# 6coils-1-discrete.net
KiCad netlist of a schematic drawn in EasyEDA
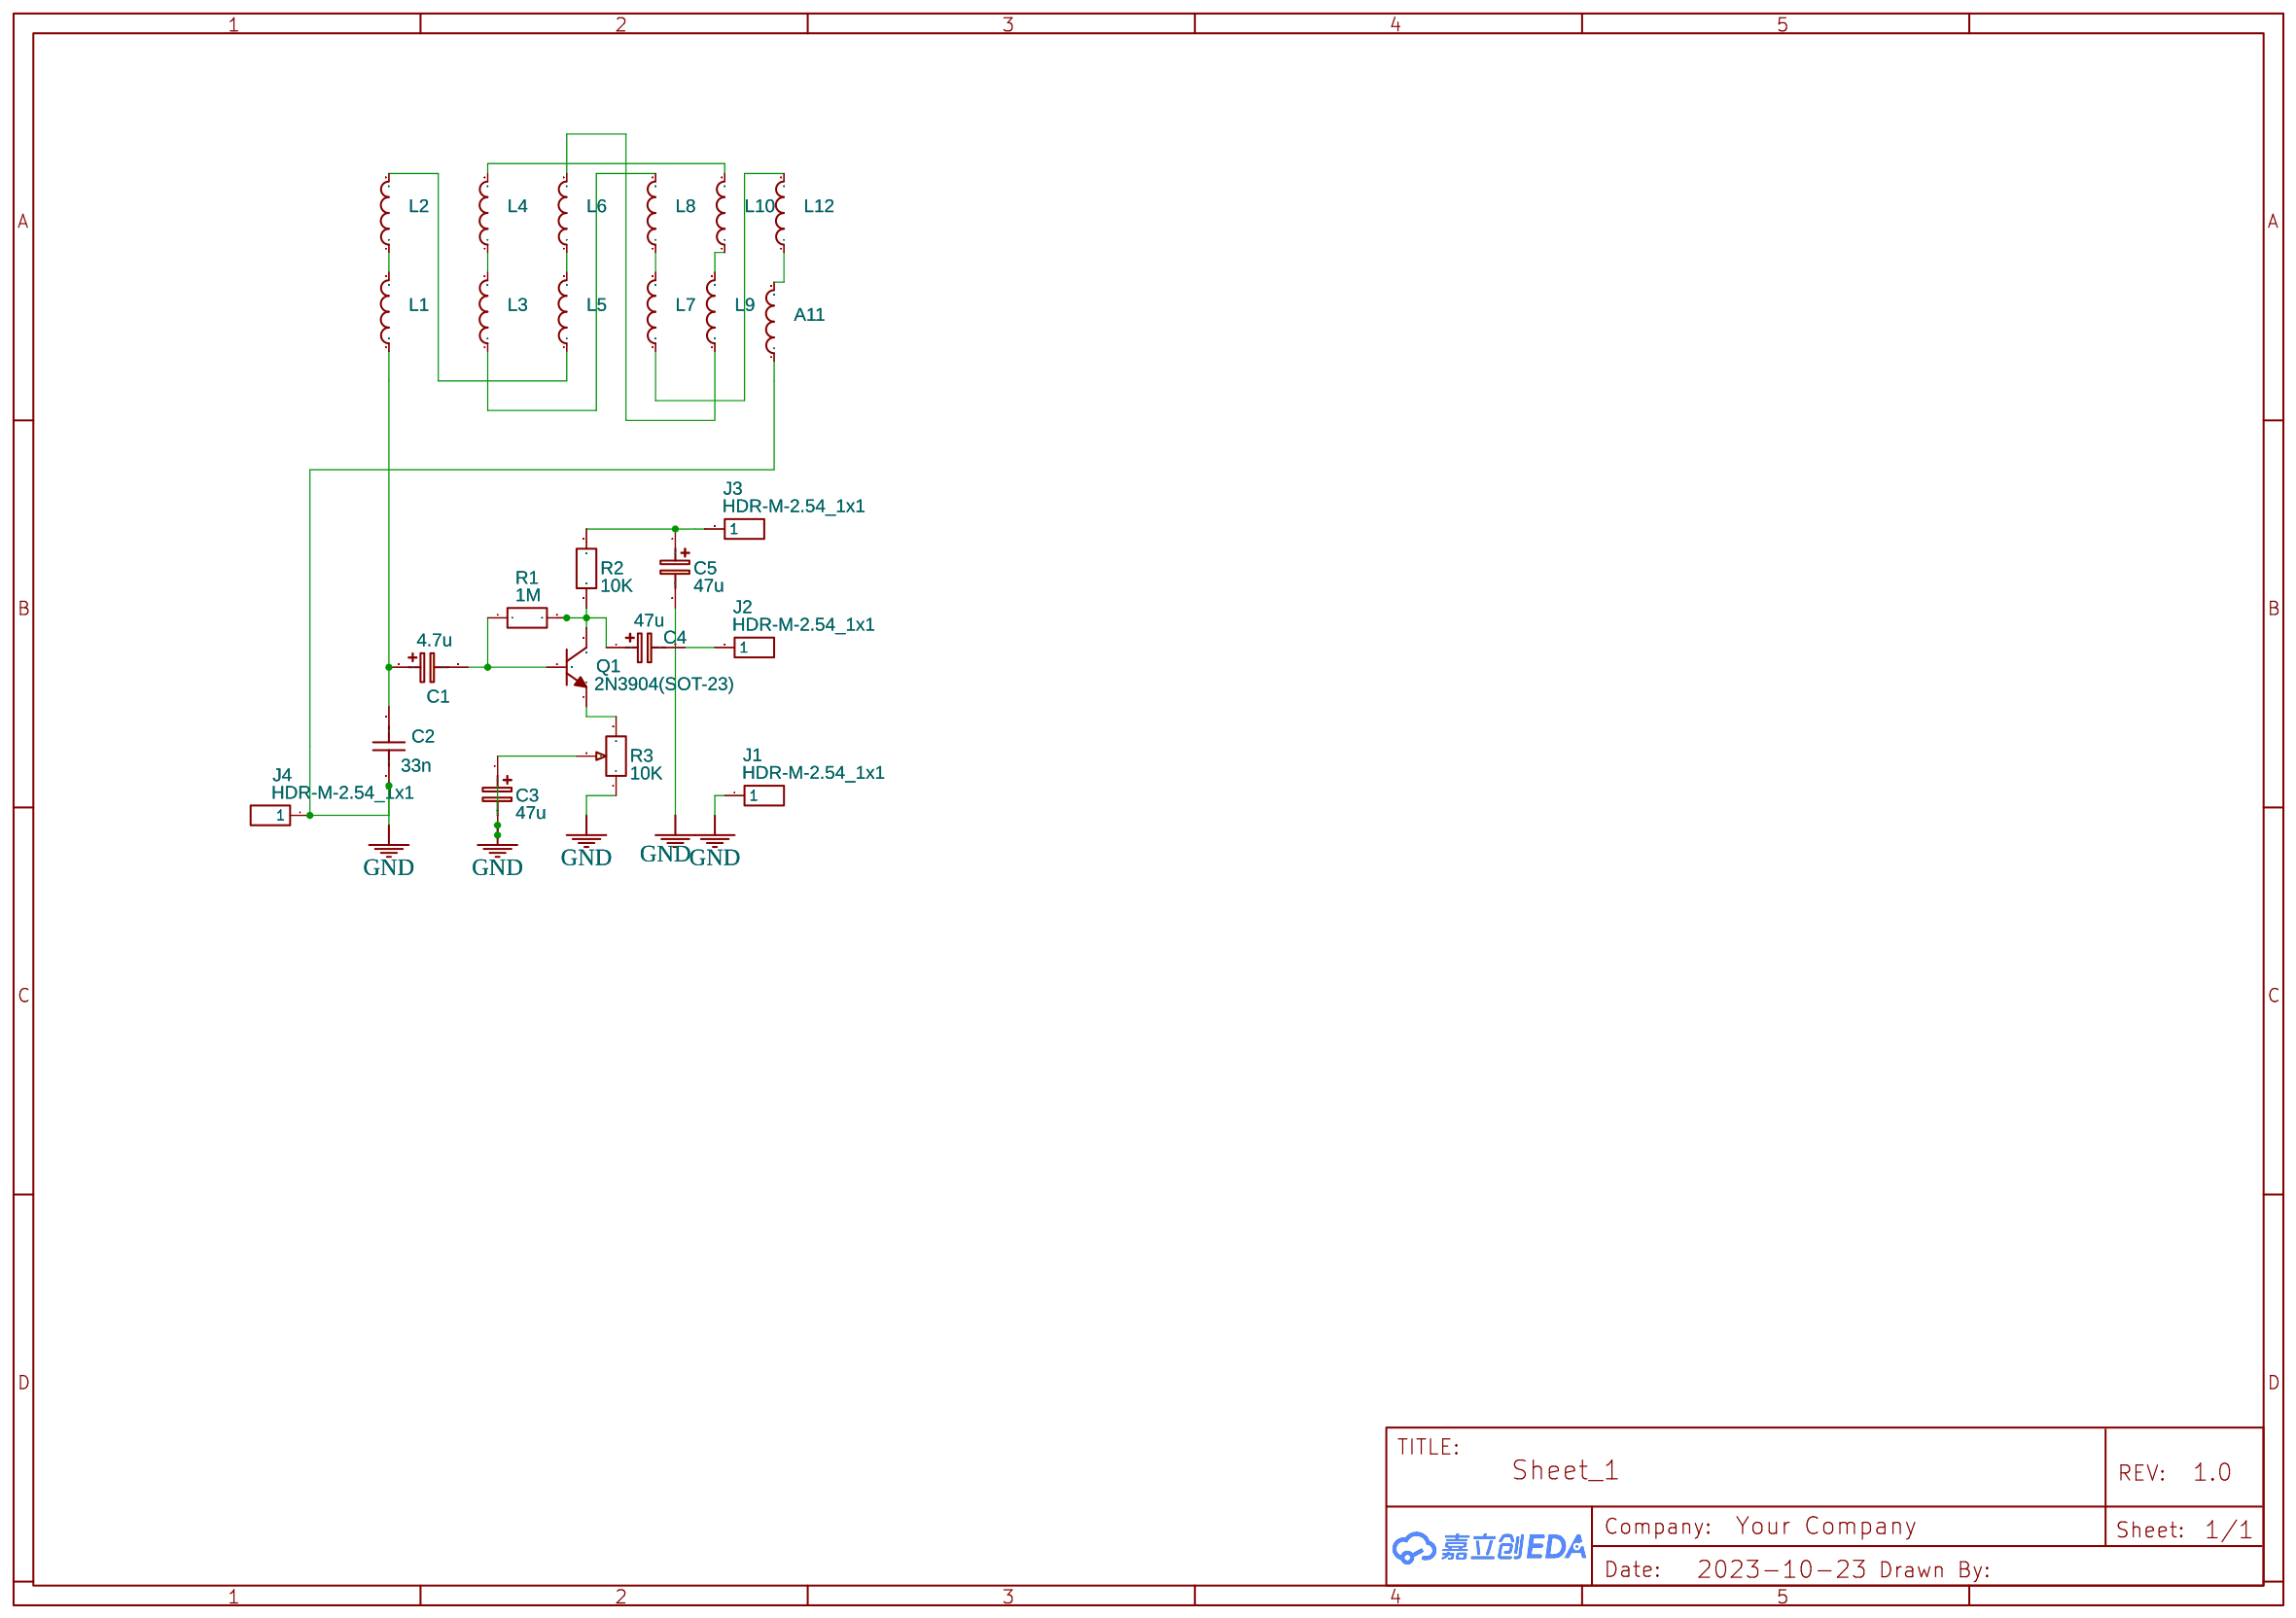
[diagram p0: schematic sheet]

(export (version "E")
  (design (tool "Eeschema 10.0.6"))
  (components
    (comp (ref "A11")
      (value "INDUCTOR_SMD:L_COILCRAFT_XXL4040")
      (fields (field (name "Manufacturer Part") "Inductor_SMD:L_Coilcraft_XxL4040"))
      (libsource (lib "") (part "INDUCTOR_SMD{colon}L_COILCRAFT_XXL4040_2"))
    )
    (comp (ref "C1") (value "4.7u") (libsource (lib "") (part "C_Tan_SMD_A_EU_1")))
    (comp (ref "C2") (value "33n") (libsource (lib "") (part "C_0603_US")))
    (comp (ref "C3") (value "47u") (libsource (lib "") (part "C_Tan_SMD_A_EU_2")))
    (comp (ref "C4") (value "47u") (libsource (lib "") (part "C_Tan_SMD_A_EU_3")))
    (comp (ref "C5") (value "47u") (libsource (lib "") (part "C_Tan_SMD_A_EU")))
    (comp (ref "J1")
      (value "HDR-M-2.54_1x1")
      (fields (field (name "BOM_Supplier Part") "C81276"))
      (libsource (lib "") (part "HDR-M-2.54_1x1"))
    )
    (comp (ref "J2")
      (value "HDR-M-2.54_1x1")
      (fields (field (name "BOM_Supplier Part") "C81276"))
      (libsource (lib "") (part "HDR-M-2.54_1x1"))
    )
    (comp (ref "J3")
      (value "HDR-M-2.54_1x1")
      (fields (field (name "BOM_Supplier Part") "C81276"))
      (libsource (lib "") (part "HDR-M-2.54_1x1"))
    )
    (comp (ref "J4")
      (value "HDR-M-2.54_1x1")
      (fields (field (name "BOM_Supplier Part") "C81276"))
      (libsource (lib "") (part "HDR-M-2.54_1x1_1"))
    )
    (comp (ref "L1")
      (value "INDUCTOR_SMD:L_COILCRAFT_XXL4040")
      (fields (field (name "Manufacturer Part") "Inductor_SMD:L_Coilcraft_XxL4040"))
      (libsource (lib "") (part "INDUCTOR_SMD{colon}L_COILCRAFT_XXL4040"))
    )
    (comp (ref "L2")
      (value "INDUCTOR_SMD:L_COILCRAFT_XXL4040")
      (fields (field (name "Manufacturer Part") "Inductor_SMD:L_Coilcraft_XxL4040"))
      (libsource (lib "") (part "INDUCTOR_SMD{colon}L_COILCRAFT_XXL4040"))
    )
    (comp (ref "L3")
      (value "INDUCTOR_SMD:L_COILCRAFT_XXL4040")
      (fields (field (name "Manufacturer Part") "Inductor_SMD:L_Coilcraft_XxL4040"))
      (libsource (lib "") (part "INDUCTOR_SMD{colon}L_COILCRAFT_XXL4040"))
    )
    (comp (ref "L4")
      (value "INDUCTOR_SMD:L_COILCRAFT_XXL4040")
      (fields (field (name "Manufacturer Part") "Inductor_SMD:L_Coilcraft_XxL4040"))
      (libsource (lib "") (part "INDUCTOR_SMD{colon}L_COILCRAFT_XXL4040"))
    )
    (comp (ref "L5")
      (value "INDUCTOR_SMD:L_COILCRAFT_XXL4040")
      (fields (field (name "Manufacturer Part") "Inductor_SMD:L_Coilcraft_XxL4040"))
      (libsource (lib "") (part "INDUCTOR_SMD{colon}L_COILCRAFT_XXL4040_1"))
    )
    (comp (ref "L6")
      (value "INDUCTOR_SMD:L_COILCRAFT_XXL4040")
      (fields (field (name "Manufacturer Part") "Inductor_SMD:L_Coilcraft_XxL4040"))
      (libsource (lib "") (part "INDUCTOR_SMD{colon}L_COILCRAFT_XXL4040_1"))
    )
    (comp (ref "L7")
      (value "INDUCTOR_SMD:L_COILCRAFT_XXL4040")
      (fields (field (name "Manufacturer Part") "Inductor_SMD:L_Coilcraft_XxL4040"))
      (libsource (lib "") (part "INDUCTOR_SMD{colon}L_COILCRAFT_XXL4040_1"))
    )
    (comp (ref "L8")
      (value "INDUCTOR_SMD:L_COILCRAFT_XXL4040")
      (fields (field (name "Manufacturer Part") "Inductor_SMD:L_Coilcraft_XxL4040"))
      (libsource (lib "") (part "INDUCTOR_SMD{colon}L_COILCRAFT_XXL4040_1"))
    )
    (comp (ref "L9")
      (value "INDUCTOR_SMD:L_COILCRAFT_XXL4040")
      (fields (field (name "Manufacturer Part") "Inductor_SMD:L_Coilcraft_XxL4040"))
      (libsource (lib "") (part "INDUCTOR_SMD{colon}L_COILCRAFT_XXL4040_1"))
    )
    (comp (ref "L10")
      (value "INDUCTOR_SMD:L_COILCRAFT_XXL4040")
      (fields (field (name "Manufacturer Part") "Inductor_SMD:L_Coilcraft_XxL4040"))
      (libsource (lib "") (part "INDUCTOR_SMD{colon}L_COILCRAFT_XXL4040_1"))
    )
    (comp (ref "L12")
      (value "INDUCTOR_SMD:L_COILCRAFT_XXL4040")
      (fields (field (name "Manufacturer Part") "Inductor_SMD:L_Coilcraft_XxL4040"))
      (libsource (lib "") (part "INDUCTOR_SMD{colon}L_COILCRAFT_XXL4040_1"))
    )
    (comp (ref "Q1")
      (value "2N3904(SOT-23)")
      (fields
        (field (name "BOM_Manufacturer Part") "2n3904S-RTK/PS")
        (field (name "BOM_Supplier Part") "C18536")
      )
      (libsource (lib "") (part "2N3904(SOT-23)"))
    )
    (comp (ref "R1") (value "1M") (libsource (lib "") (part "R_0603_EU")))
    (comp (ref "R2") (value "10K") (libsource (lib "") (part "R_0603_EU_1")))
    (comp (ref "R3")
      (value "10K")
      (fields (field (name "Manufacturer Part") "RM063-103 10K") (field (name "Manufacturer") "JML"))
      (libsource (lib "") (part "RM063-103 10K"))
    )
  )
  (nets
    (net (code "1") (name "GND") (class "Default")
      (node (ref "A11") (pin "1") (pinfunction "1_1") (pintype "unspecified"))
      (node (ref "C2") (pin "1") (pinfunction "1_1") (pintype "unspecified"))
      (node (ref "C3") (pin "2") (pinfunction "2_2") (pintype "unspecified"))
      (node (ref "C5") (pin "2") (pinfunction "2_2") (pintype "unspecified"))
      (node (ref "J1") (pin "1") (pinfunction "1_1") (pintype "input"))
      (node (ref "J4") (pin "1") (pinfunction "1_1") (pintype "input"))
      (node (ref "R3") (pin "1") (pinfunction "1_1") (pintype "input"))
    )
    (net (code "2") (name "Net-(A11-Pad2)") (class "Default")
      (node (ref "A11") (pin "2") (pinfunction "2_2") (pintype "unspecified"))
      (node (ref "L12") (pin "1") (pinfunction "1_1") (pintype "unspecified"))
    )
    (net (code "3") (name "Net-(C1-Pad1)") (class "Default")
      (node (ref "C1") (pin "1") (pinfunction "1_1") (pintype "unspecified"))
      (node (ref "C2") (pin "2") (pinfunction "2_2") (pintype "unspecified"))
      (node (ref "L1") (pin "1") (pinfunction "1_1") (pintype "unspecified"))
    )
    (net (code "4") (name "Net-(C3-Pad1)") (class "Default")
      (node (ref "C3") (pin "1") (pinfunction "1_1") (pintype "unspecified"))
      (node (ref "R3") (pin "2") (pinfunction "2_2") (pintype "input"))
    )
    (net (code "5") (name "Net-(C4-Pad2)") (class "Default")
      (node (ref "C4") (pin "2") (pinfunction "2_2") (pintype "unspecified"))
      (node (ref "J2") (pin "1") (pinfunction "1_1") (pintype "input"))
    )
    (net (code "6") (name "Net-(C5-Pad1)") (class "Default")
      (node (ref "C5") (pin "1") (pinfunction "1_1") (pintype "unspecified"))
      (node (ref "J3") (pin "1") (pinfunction "1_1") (pintype "input"))
      (node (ref "R2") (pin "2") (pinfunction "2_2") (pintype "unspecified"))
    )
    (net (code "7") (name "Net-(L1-Pad2)") (class "Default")
      (node (ref "L1") (pin "2") (pinfunction "2_2") (pintype "unspecified"))
      (node (ref "L2") (pin "1") (pinfunction "1_1") (pintype "unspecified"))
    )
    (net (code "8") (name "Net-(L2-Pad2)") (class "Default")
      (node (ref "L2") (pin "2") (pinfunction "2_2") (pintype "unspecified"))
      (node (ref "L5") (pin "1") (pinfunction "1_1") (pintype "unspecified"))
    )
    (net (code "9") (name "Net-(L3-Pad1)") (class "Default")
      (node (ref "L3") (pin "1") (pinfunction "1_1") (pintype "unspecified"))
      (node (ref "L8") (pin "2") (pinfunction "2_2") (pintype "unspecified"))
    )
    (net (code "10") (name "Net-(L3-Pad2)") (class "Default")
      (node (ref "L3") (pin "2") (pinfunction "2_2") (pintype "unspecified"))
      (node (ref "L4") (pin "1") (pinfunction "1_1") (pintype "unspecified"))
    )
    (net (code "11") (name "Net-(L5-Pad2)") (class "Default")
      (node (ref "L5") (pin "2") (pinfunction "2_2") (pintype "unspecified"))
      (node (ref "L6") (pin "1") (pinfunction "1_1") (pintype "unspecified"))
    )
    (net (code "12") (name "Net-(L6-Pad2)") (class "Default")
      (node (ref "L6") (pin "2") (pinfunction "2_2") (pintype "unspecified"))
      (node (ref "L9") (pin "1") (pinfunction "1_1") (pintype "unspecified"))
    )
    (net (code "13") (name "Net-(L7-Pad2)") (class "Default")
      (node (ref "L7") (pin "2") (pinfunction "2_2") (pintype "unspecified"))
      (node (ref "L8") (pin "1") (pinfunction "1_1") (pintype "unspecified"))
    )
    (net (code "14") (name "Net-(L10-Pad1)") (class "Default")
      (node (ref "L10") (pin "1") (pinfunction "1_1") (pintype "unspecified"))
      (node (ref "L9") (pin "2") (pinfunction "2_2") (pintype "unspecified"))
    )
    (net (code "15") (name "Net-(L10-Pad2)") (class "Default")
      (node (ref "L10") (pin "2") (pinfunction "2_2") (pintype "unspecified"))
      (node (ref "L4") (pin "2") (pinfunction "2_2") (pintype "unspecified"))
    )
    (net (code "16") (name "Net-(L12-Pad2)") (class "Default")
      (node (ref "L12") (pin "2") (pinfunction "2_2") (pintype "unspecified"))
      (node (ref "L7") (pin "1") (pinfunction "1_1") (pintype "unspecified"))
    )
    (net (code "17") (name "Net-(Q1-B)") (class "Default")
      (node (ref "C1") (pin "2") (pinfunction "2_2") (pintype "unspecified"))
      (node (ref "Q1") (pin "2") (pinfunction "B_2") (pintype "input"))
      (node (ref "R1") (pin "1") (pinfunction "1_1") (pintype "unspecified"))
    )
    (net (code "18") (name "Net-(Q1-C)") (class "Default")
      (node (ref "C4") (pin "1") (pinfunction "1_1") (pintype "unspecified"))
      (node (ref "Q1") (pin "3") (pinfunction "C_3") (pintype "input"))
      (node (ref "R1") (pin "2") (pinfunction "2_2") (pintype "unspecified"))
      (node (ref "R2") (pin "1") (pinfunction "1_1") (pintype "unspecified"))
    )
    (net (code "19") (name "Net-(Q1-E)") (class "Default")
      (node (ref "Q1") (pin "1") (pinfunction "E_1") (pintype "input"))
      (node (ref "R3") (pin "3") (pinfunction "3_3") (pintype "input"))
    )
  )
)
